# NMOS_DESIGN.net
KiCad netlist of a schematic drawn in EAGLE
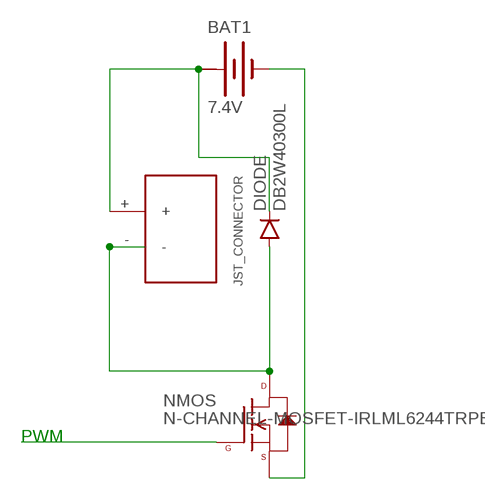
[diagram p0: schematic, sheet 1]

(export (version "E")
  (design (tool "Eeschema 10.0.6"))
  (components
    (comp (ref "BAT1")
      (value "7.4V")
      (footprint "eagle-import:BATTERY")
      (libsource (lib "eagle-import") (part "BATTERY"))
    )
    (comp (ref "DIODE")
      (value "DB2W40300L")
      (footprint "eagle-import:MINI2-F3-B")
      (libsource (lib "eagle-import") (part "DB2W40300L"))
    )
    (comp (ref "MOTOR")
      (value "JST_CONNECTOR_FEMALE")
      (footprint "eagle-import:JST_CONNECTOR_FEMALE")
      (libsource (lib "eagle-import") (part "JST_CONNECTOR_FEMALE"))
    )
    (comp (ref "NMOS")
      (value "N-CHANNEL-MOSFET-IRLML6244TRPBF")
      (footprint "eagle-import:SOT23-3")
      (libsource (lib "eagle-import") (part "N-CHANNEL-MOSFET-IRLML6244TRPBF"))
    )
  )
  (nets
    (net (code "1") (name "/+") (class "Default")
      (node (ref "BAT1") (pin "+@1") (pinfunction "+_+@1") (pintype "power_in"))
    )
    (net (code "2") (name "Net-(DIODE-GPIN)") (class "Default")
      (node (ref "BAT1") (pin "+") (pinfunction "+_+") (pintype "power_in"))
      (node (ref "DIODE") (pin "NEG") (pinfunction "GPIN_NEG") (pintype "passive"))
      (node (ref "MOTOR") (pin "+") (pinfunction "+_+") (pintype "bidirectional"))
    )
    (net (code "3") (name "Net-(DIODE-PPIN)") (class "Default")
      (node (ref "DIODE") (pin "POS") (pinfunction "PPIN_POS") (pintype "passive"))
      (node (ref "MOTOR") (pin "-") (pinfunction "-_-") (pintype "bidirectional"))
      (node (ref "NMOS") (pin "3") (pinfunction "D_3") (pintype "passive"))
    )
    (net (code "4") (name "Net-(NMOS-S)") (class "Default")
      (node (ref "BAT1") (pin "-") (pinfunction "-_-") (pintype "power_in"))
      (node (ref "NMOS") (pin "2") (pinfunction "S_2") (pintype "passive"))
    )
    (net (code "5") (name "unconnected-(NMOS-G-Pad1)") (class "Default")
      (node (ref "NMOS") (pin "1") (pinfunction "G_1") (pintype "passive"))
    )
  )
)
